# SCH_EspBoy.net
KiCad netlist of a schematic drawn in EasyEDA
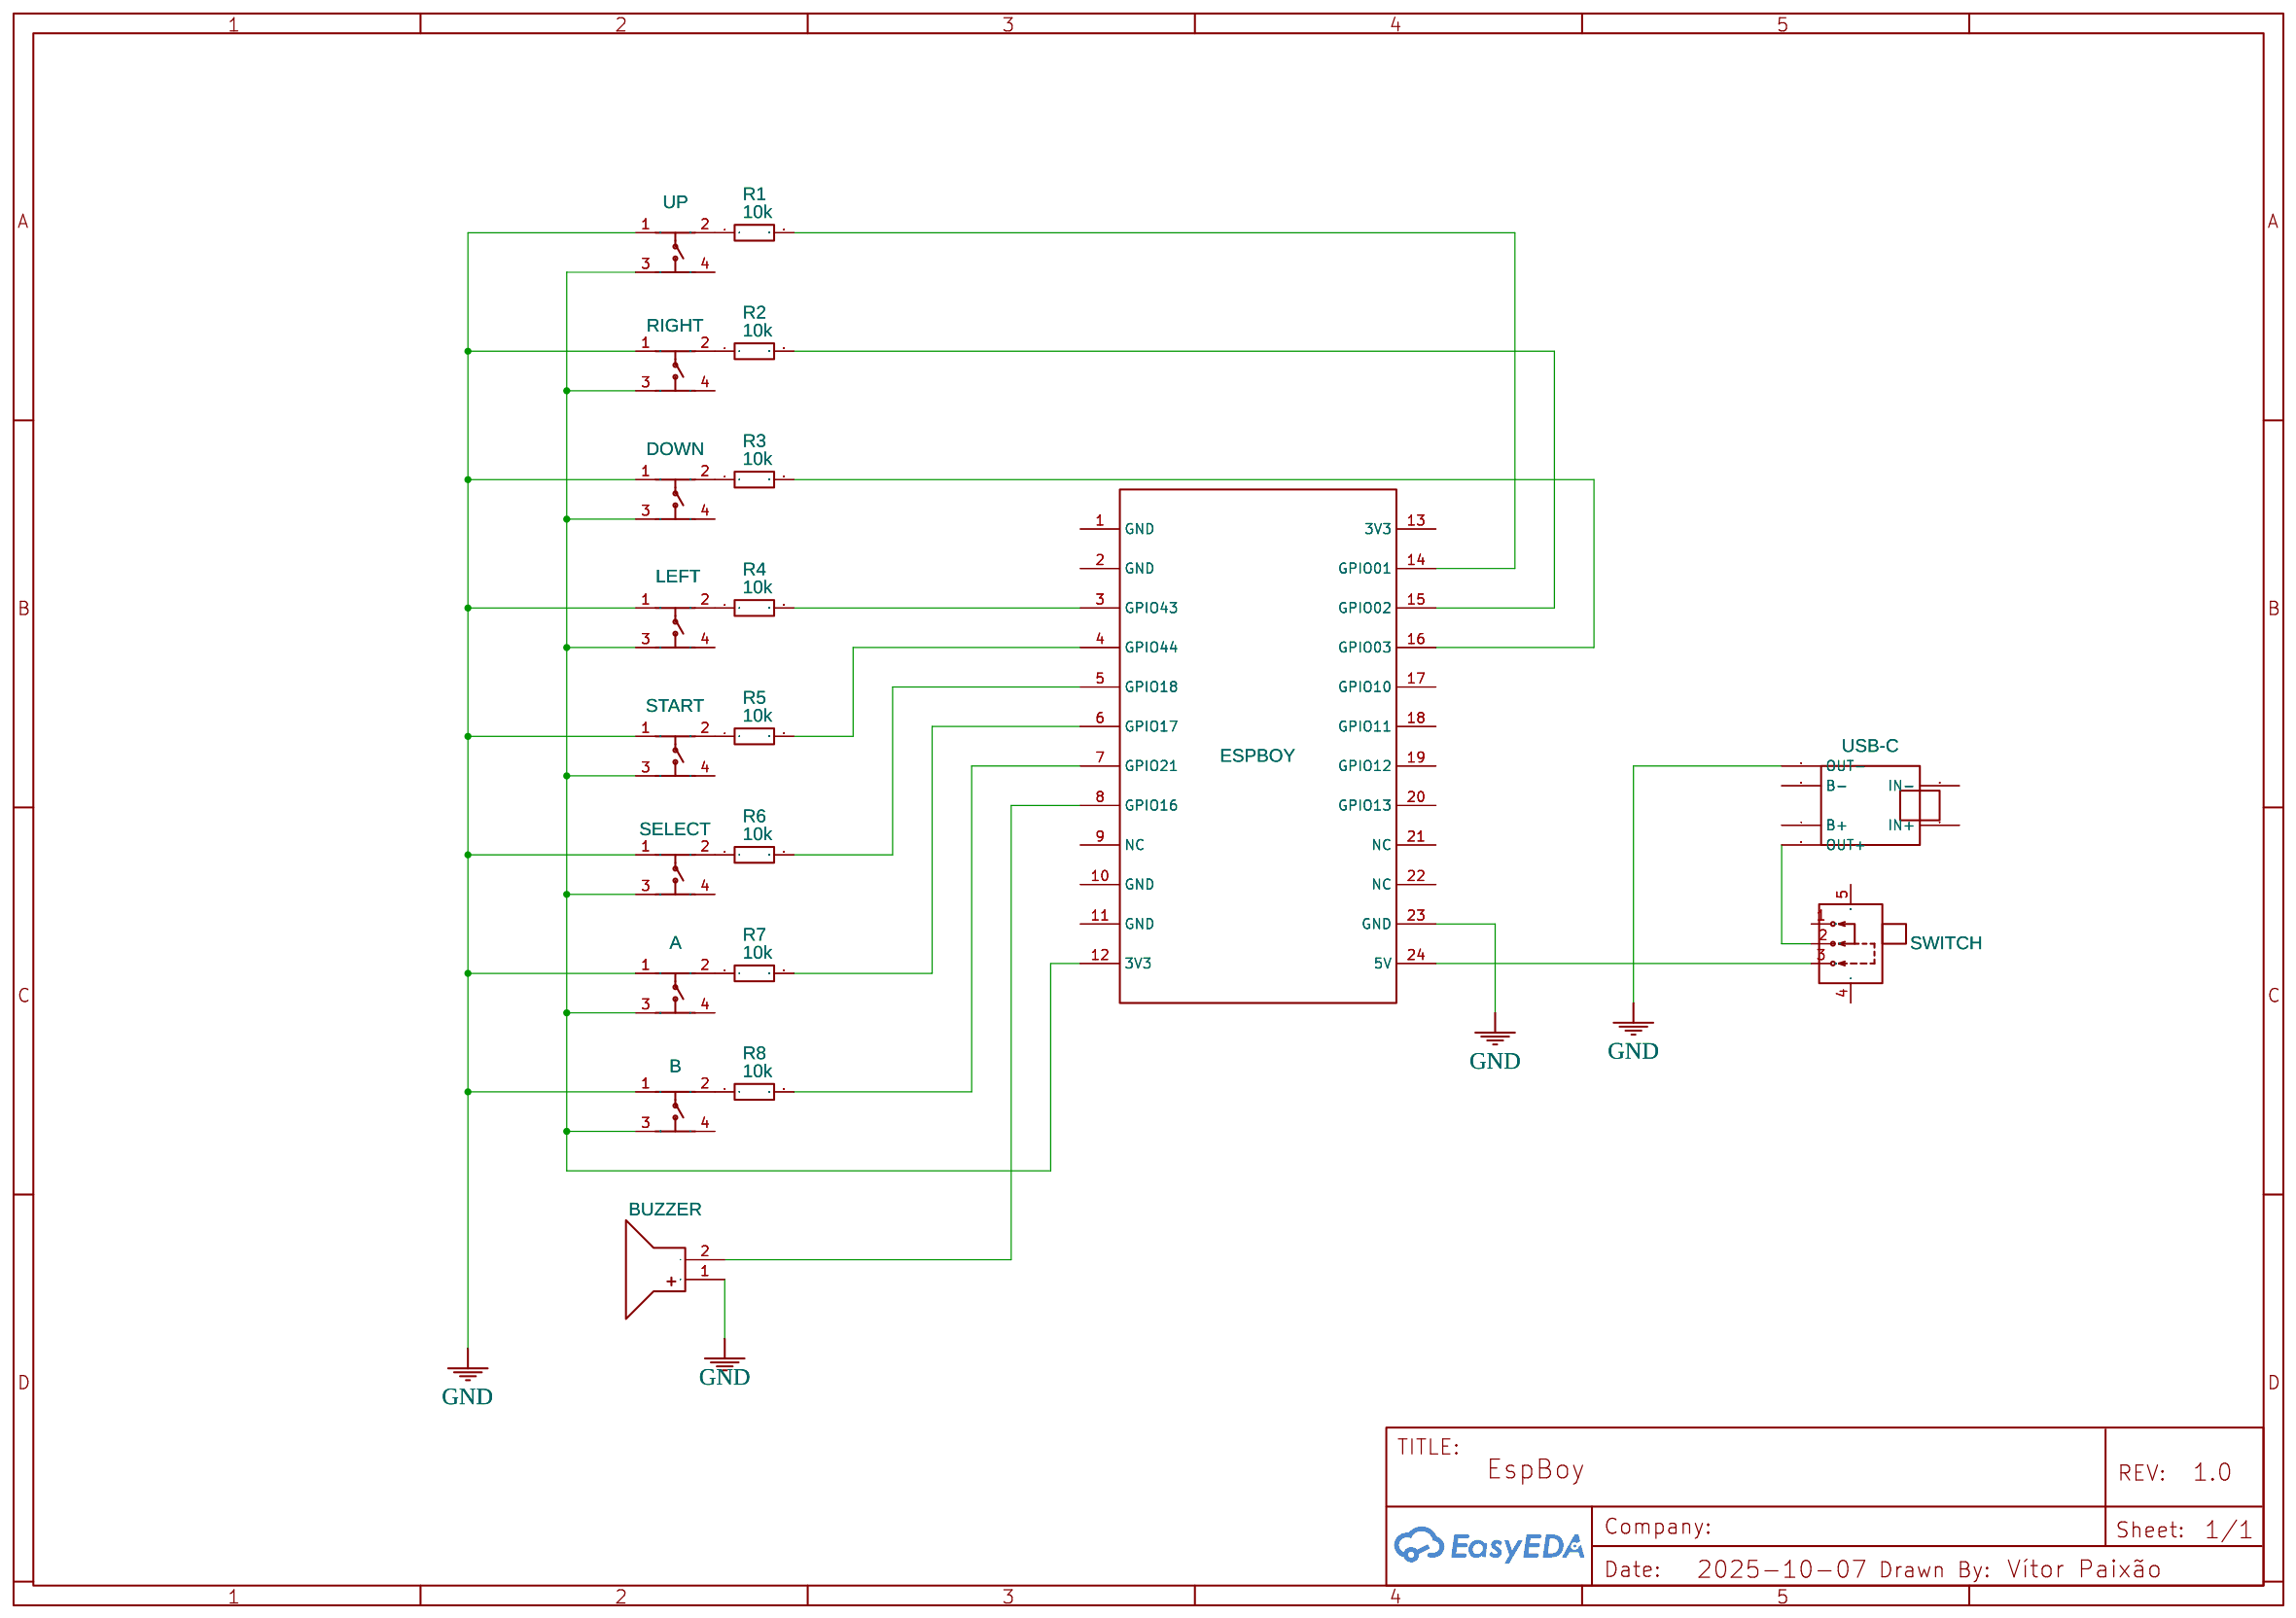
[diagram p0: schematic sheet]

(export (version "E")
  (design (tool "Eeschema 10.0.6"))
  (components
    (comp (ref "A")
      (value "TC-00121FS-080E")
      (fields (field (name "Manufacturer") "HOOYA(皓宇电子)"))
      (libsource (lib "") (part "TC-00121FS-080E_5"))
    )
    (comp (ref "B")
      (value "TC-00121FS-080E")
      (fields (field (name "Manufacturer") "HOOYA(皓宇电子)"))
      (libsource (lib "") (part "TC-00121FS-080E_7"))
    )
    (comp (ref "BUZZER")
      (value "2207-P10MM")
      (fields (field (name "Manufacturer") "XHXDZ(兴华鑫)"))
      (libsource (lib "") (part "2207-P10MM"))
    )
    (comp (ref "DOWN")
      (value "TC-00121FS-080E")
      (fields (field (name "Manufacturer") "HOOYA(皓宇电子)"))
      (libsource (lib "") (part "TC-00121FS-080E"))
    )
    (comp (ref "ESPBOY")
      (value "LILYGO T-Display S3")
      (fields (field (name "Manufacturer Part") "T-Display S3") (field (name "Manufacturer") "LILYGO"))
      (libsource (lib "") (part "LILYGO T-Display S3"))
    )
    (comp (ref "LEFT")
      (value "TC-00121FS-080E")
      (fields (field (name "Manufacturer") "HOOYA(皓宇电子)"))
      (libsource (lib "") (part "TC-00121FS-080E_1"))
    )
    (comp (ref "R1")
      (value "10k")
      (fields (field (name "Manufacturer Part") "AXIAL-0.4"))
      (libsource (lib "") (part "AXIAL-0.4"))
    )
    (comp (ref "R2")
      (value "10k")
      (fields (field (name "Manufacturer Part") "AXIAL-0.4"))
      (libsource (lib "") (part "AXIAL-0.4"))
    )
    (comp (ref "R3")
      (value "10k")
      (fields (field (name "Manufacturer Part") "AXIAL-0.4"))
      (libsource (lib "") (part "AXIAL-0.4"))
    )
    (comp (ref "R4")
      (value "10k")
      (fields (field (name "Manufacturer Part") "AXIAL-0.4"))
      (libsource (lib "") (part "AXIAL-0.4"))
    )
    (comp (ref "R5")
      (value "10k")
      (fields (field (name "Manufacturer Part") "AXIAL-0.4"))
      (libsource (lib "") (part "AXIAL-0.4"))
    )
    (comp (ref "R6")
      (value "10k")
      (fields (field (name "Manufacturer Part") "AXIAL-0.4"))
      (libsource (lib "") (part "AXIAL-0.4"))
    )
    (comp (ref "R7")
      (value "10k")
      (fields (field (name "Manufacturer Part") "AXIAL-0.4"))
      (libsource (lib "") (part "AXIAL-0.4"))
    )
    (comp (ref "R8")
      (value "10k")
      (fields (field (name "Manufacturer Part") "AXIAL-0.4"))
      (libsource (lib "") (part "AXIAL-0.4"))
    )
    (comp (ref "RIGHT")
      (value "TC-00121FS-080E")
      (fields (field (name "Manufacturer") "HOOYA(皓宇电子)"))
      (libsource (lib "") (part "TC-00121FS-080E_3"))
    )
    (comp (ref "SELECT")
      (value "TC-00121FS-080E")
      (fields (field (name "Manufacturer") "HOOYA(皓宇电子)"))
      (libsource (lib "") (part "TC-00121FS-080E_2"))
    )
    (comp (ref "START")
      (value "TC-00121FS-080E")
      (fields (field (name "Manufacturer") "HOOYA(皓宇电子)"))
      (libsource (lib "") (part "TC-00121FS-080E_4"))
    )
    (comp (ref "SWITCH")
      (value "SS12F44G5")
      (fields (field (name "Manufacturer") "HanElectricity(瀚源)"))
      (libsource (lib "") (part "SS12F44G5"))
    )
    (comp (ref "UP")
      (value "TC-00121FS-080E")
      (fields (field (name "Manufacturer") "HOOYA(皓宇电子)"))
      (libsource (lib "") (part "TC-00121FS-080E_6"))
    )
    (comp (ref "USB-C") (value "Módulo USB-C TP4056") (libsource (lib "") (part "Módulo USB-C TP4056")))
  )
  (nets
    (net (code "1") (name "GND") (class "Default")
      (node (ref "A") (pin "1") (pinfunction "1_1") (pintype "unspecified"))
      (node (ref "B") (pin "1") (pinfunction "1_1") (pintype "unspecified"))
      (node (ref "BUZZER") (pin "1") (pinfunction "+_1") (pintype "unspecified"))
      (node (ref "DOWN") (pin "1") (pinfunction "1_1") (pintype "unspecified"))
      (node (ref "ESPBOY") (pin "23") (pinfunction "GND_23") (pintype "unspecified"))
      (node (ref "LEFT") (pin "1") (pinfunction "1_1") (pintype "unspecified"))
      (node (ref "RIGHT") (pin "1") (pinfunction "1_1") (pintype "unspecified"))
      (node (ref "SELECT") (pin "1") (pinfunction "1_1") (pintype "unspecified"))
      (node (ref "START") (pin "1") (pinfunction "1_1") (pintype "unspecified"))
      (node (ref "UP") (pin "1") (pinfunction "1_1") (pintype "unspecified"))
      (node (ref "USB-C") (pin "6") (pinfunction "OUT-_6") (pintype "unspecified"))
    )
    (net (code "2") (name "Net-(A-Pad2)") (class "Default")
      (node (ref "A") (pin "2") (pinfunction "2_2") (pintype "unspecified"))
      (node (ref "R7") (pin "1") (pinfunction "1_1") (pintype "unspecified"))
    )
    (net (code "3") (name "Net-(A-Pad3)") (class "Default")
      (node (ref "A") (pin "3") (pinfunction "3_3") (pintype "unspecified"))
      (node (ref "B") (pin "3") (pinfunction "3_3") (pintype "unspecified"))
      (node (ref "DOWN") (pin "3") (pinfunction "3_3") (pintype "unspecified"))
      (node (ref "ESPBOY") (pin "12") (pinfunction "3V3_12") (pintype "unspecified"))
      (node (ref "LEFT") (pin "3") (pinfunction "3_3") (pintype "unspecified"))
      (node (ref "RIGHT") (pin "3") (pinfunction "3_3") (pintype "unspecified"))
      (node (ref "SELECT") (pin "3") (pinfunction "3_3") (pintype "unspecified"))
      (node (ref "START") (pin "3") (pinfunction "3_3") (pintype "unspecified"))
      (node (ref "UP") (pin "3") (pinfunction "3_3") (pintype "unspecified"))
    )
    (net (code "4") (name "Net-(B-Pad2)") (class "Default")
      (node (ref "B") (pin "2") (pinfunction "2_2") (pintype "unspecified"))
      (node (ref "R8") (pin "1") (pinfunction "1_1") (pintype "unspecified"))
    )
    (net (code "5") (name "Net-(BUZZER--)") (class "Default")
      (node (ref "BUZZER") (pin "2") (pinfunction "-_2") (pintype "unspecified"))
      (node (ref "ESPBOY") (pin "8") (pinfunction "GPIO16_8") (pintype "unspecified"))
    )
    (net (code "6") (name "Net-(DOWN-Pad2)") (class "Default")
      (node (ref "DOWN") (pin "2") (pinfunction "2_2") (pintype "unspecified"))
      (node (ref "R3") (pin "1") (pinfunction "1_1") (pintype "unspecified"))
    )
    (net (code "7") (name "Net-(ESPBOY-5V)") (class "Default")
      (node (ref "ESPBOY") (pin "24") (pinfunction "5V_24") (pintype "unspecified"))
      (node (ref "SWITCH") (pin "3") (pinfunction "3_3") (pintype "unspecified"))
    )
    (net (code "8") (name "Net-(ESPBOY-GPIO01)") (class "Default")
      (node (ref "ESPBOY") (pin "14") (pinfunction "GPIO01_14") (pintype "unspecified"))
      (node (ref "R1") (pin "2") (pinfunction "2_2") (pintype "unspecified"))
    )
    (net (code "9") (name "Net-(ESPBOY-GPIO02)") (class "Default")
      (node (ref "ESPBOY") (pin "15") (pinfunction "GPIO02_15") (pintype "unspecified"))
      (node (ref "R2") (pin "2") (pinfunction "2_2") (pintype "unspecified"))
    )
    (net (code "10") (name "Net-(ESPBOY-GPIO03)") (class "Default")
      (node (ref "ESPBOY") (pin "16") (pinfunction "GPIO03_16") (pintype "unspecified"))
      (node (ref "R3") (pin "2") (pinfunction "2_2") (pintype "unspecified"))
    )
    (net (code "11") (name "Net-(ESPBOY-GPIO17)") (class "Default")
      (node (ref "ESPBOY") (pin "6") (pinfunction "GPIO17_6") (pintype "unspecified"))
      (node (ref "R7") (pin "2") (pinfunction "2_2") (pintype "unspecified"))
    )
    (net (code "12") (name "Net-(ESPBOY-GPIO18)") (class "Default")
      (node (ref "ESPBOY") (pin "5") (pinfunction "GPIO18_5") (pintype "unspecified"))
      (node (ref "R6") (pin "2") (pinfunction "2_2") (pintype "unspecified"))
    )
    (net (code "13") (name "Net-(ESPBOY-GPIO21)") (class "Default")
      (node (ref "ESPBOY") (pin "7") (pinfunction "GPIO21_7") (pintype "unspecified"))
      (node (ref "R8") (pin "2") (pinfunction "2_2") (pintype "unspecified"))
    )
    (net (code "14") (name "Net-(ESPBOY-GPIO43)") (class "Default")
      (node (ref "ESPBOY") (pin "3") (pinfunction "GPIO43_3") (pintype "unspecified"))
      (node (ref "R4") (pin "2") (pinfunction "2_2") (pintype "unspecified"))
    )
    (net (code "15") (name "Net-(ESPBOY-GPIO44)") (class "Default")
      (node (ref "ESPBOY") (pin "4") (pinfunction "GPIO44_4") (pintype "unspecified"))
      (node (ref "R5") (pin "2") (pinfunction "2_2") (pintype "unspecified"))
    )
    (net (code "16") (name "Net-(LEFT-Pad2)") (class "Default")
      (node (ref "LEFT") (pin "2") (pinfunction "2_2") (pintype "unspecified"))
      (node (ref "R4") (pin "1") (pinfunction "1_1") (pintype "unspecified"))
    )
    (net (code "17") (name "Net-(R1-Pad1)") (class "Default")
      (node (ref "R1") (pin "1") (pinfunction "1_1") (pintype "unspecified"))
      (node (ref "UP") (pin "2") (pinfunction "2_2") (pintype "unspecified"))
    )
    (net (code "18") (name "Net-(R2-Pad1)") (class "Default")
      (node (ref "R2") (pin "1") (pinfunction "1_1") (pintype "unspecified"))
      (node (ref "RIGHT") (pin "2") (pinfunction "2_2") (pintype "unspecified"))
    )
    (net (code "19") (name "Net-(R5-Pad1)") (class "Default")
      (node (ref "R5") (pin "1") (pinfunction "1_1") (pintype "unspecified"))
      (node (ref "START") (pin "2") (pinfunction "2_2") (pintype "unspecified"))
    )
    (net (code "20") (name "Net-(R6-Pad1)") (class "Default")
      (node (ref "R6") (pin "1") (pinfunction "1_1") (pintype "unspecified"))
      (node (ref "SELECT") (pin "2") (pinfunction "2_2") (pintype "unspecified"))
    )
    (net (code "21") (name "Net-(USB-C-OUT+)") (class "Default")
      (node (ref "SWITCH") (pin "2") (pinfunction "2_2") (pintype "unspecified"))
      (node (ref "USB-C") (pin "3") (pinfunction "OUT+_3") (pintype "unspecified"))
    )
    (net (code "22") (name "unconnected-(A-Pad4)") (class "Default")
      (node (ref "A") (pin "4") (pinfunction "4_4") (pintype "unspecified"))
    )
    (net (code "23") (name "unconnected-(B-Pad4)") (class "Default")
      (node (ref "B") (pin "4") (pinfunction "4_4") (pintype "unspecified"))
    )
    (net (code "24") (name "unconnected-(DOWN-Pad4)") (class "Default")
      (node (ref "DOWN") (pin "4") (pinfunction "4_4") (pintype "unspecified"))
    )
    (net (code "25") (name "unconnected-(ESPBOY-3V3-Pad13)") (class "Default")
      (node (ref "ESPBOY") (pin "13") (pinfunction "3V3_13") (pintype "unspecified"))
    )
    (net (code "26") (name "unconnected-(ESPBOY-GND-Pad1)") (class "Default")
      (node (ref "ESPBOY") (pin "1") (pinfunction "GND_1") (pintype "unspecified"))
    )
    (net (code "27") (name "unconnected-(ESPBOY-GND-Pad2)") (class "Default")
      (node (ref "ESPBOY") (pin "2") (pinfunction "GND_2") (pintype "unspecified"))
    )
    (net (code "28") (name "unconnected-(ESPBOY-GND-Pad10)") (class "Default")
      (node (ref "ESPBOY") (pin "10") (pinfunction "GND_10") (pintype "unspecified"))
    )
    (net (code "29") (name "unconnected-(ESPBOY-GND-Pad11)") (class "Default")
      (node (ref "ESPBOY") (pin "11") (pinfunction "GND_11") (pintype "unspecified"))
    )
    (net (code "30") (name "unconnected-(ESPBOY-GPIO10-Pad17)") (class "Default")
      (node (ref "ESPBOY") (pin "17") (pinfunction "GPIO10_17") (pintype "unspecified"))
    )
    (net (code "31") (name "unconnected-(ESPBOY-GPIO11-Pad18)") (class "Default")
      (node (ref "ESPBOY") (pin "18") (pinfunction "GPIO11_18") (pintype "unspecified"))
    )
    (net (code "32") (name "unconnected-(ESPBOY-GPIO12-Pad19)") (class "Default")
      (node (ref "ESPBOY") (pin "19") (pinfunction "GPIO12_19") (pintype "unspecified"))
    )
    (net (code "33") (name "unconnected-(ESPBOY-GPIO13-Pad20)") (class "Default")
      (node (ref "ESPBOY") (pin "20") (pinfunction "GPIO13_20") (pintype "unspecified"))
    )
    (net (code "34") (name "unconnected-(ESPBOY-NC-Pad9)") (class "Default")
      (node (ref "ESPBOY") (pin "9") (pinfunction "NC_9") (pintype "unspecified"))
    )
    (net (code "35") (name "unconnected-(ESPBOY-NC-Pad21)") (class "Default")
      (node (ref "ESPBOY") (pin "21") (pinfunction "NC_21") (pintype "unspecified"))
    )
    (net (code "36") (name "unconnected-(ESPBOY-NC-Pad22)") (class "Default")
      (node (ref "ESPBOY") (pin "22") (pinfunction "NC_22") (pintype "unspecified"))
    )
    (net (code "37") (name "unconnected-(LEFT-Pad4)") (class "Default")
      (node (ref "LEFT") (pin "4") (pinfunction "4_4") (pintype "unspecified"))
    )
    (net (code "38") (name "unconnected-(RIGHT-Pad4)") (class "Default")
      (node (ref "RIGHT") (pin "4") (pinfunction "4_4") (pintype "unspecified"))
    )
    (net (code "39") (name "unconnected-(SELECT-Pad4)") (class "Default")
      (node (ref "SELECT") (pin "4") (pinfunction "4_4") (pintype "unspecified"))
    )
    (net (code "40") (name "unconnected-(START-Pad4)") (class "Default")
      (node (ref "START") (pin "4") (pinfunction "4_4") (pintype "unspecified"))
    )
    (net (code "41") (name "unconnected-(SWITCH-Pad1)") (class "Default")
      (node (ref "SWITCH") (pin "1") (pinfunction "1_1") (pintype "unspecified"))
    )
    (net (code "42") (name "unconnected-(SWITCH-Pad4)") (class "Default")
      (node (ref "SWITCH") (pin "4") (pinfunction "4_4") (pintype "unspecified"))
    )
    (net (code "43") (name "unconnected-(SWITCH-Pad5)") (class "Default")
      (node (ref "SWITCH") (pin "5") (pinfunction "5_5") (pintype "unspecified"))
    )
    (net (code "44") (name "unconnected-(UP-Pad4)") (class "Default")
      (node (ref "UP") (pin "4") (pinfunction "4_4") (pintype "unspecified"))
    )
    (net (code "45") (name "unconnected-(USB-C-B+-Pad4)") (class "Default")
      (node (ref "USB-C") (pin "4") (pinfunction "B+_4") (pintype "unspecified"))
    )
    (net (code "46") (name "unconnected-(USB-C-B--Pad5)") (class "Default")
      (node (ref "USB-C") (pin "5") (pinfunction "B-_5") (pintype "unspecified"))
    )
    (net (code "47") (name "unconnected-(USB-C-IN+-Pad1)") (class "Default")
      (node (ref "USB-C") (pin "1") (pinfunction "IN+_1") (pintype "unspecified"))
    )
    (net (code "48") (name "unconnected-(USB-C-IN--Pad2)") (class "Default")
      (node (ref "USB-C") (pin "2") (pinfunction "IN-_2") (pintype "unspecified"))
    )
  )
)
